# SCH_Arduino_Nano_ESP32_CapibaraZero_2024.net
KiCad netlist of a schematic drawn in EasyEDA
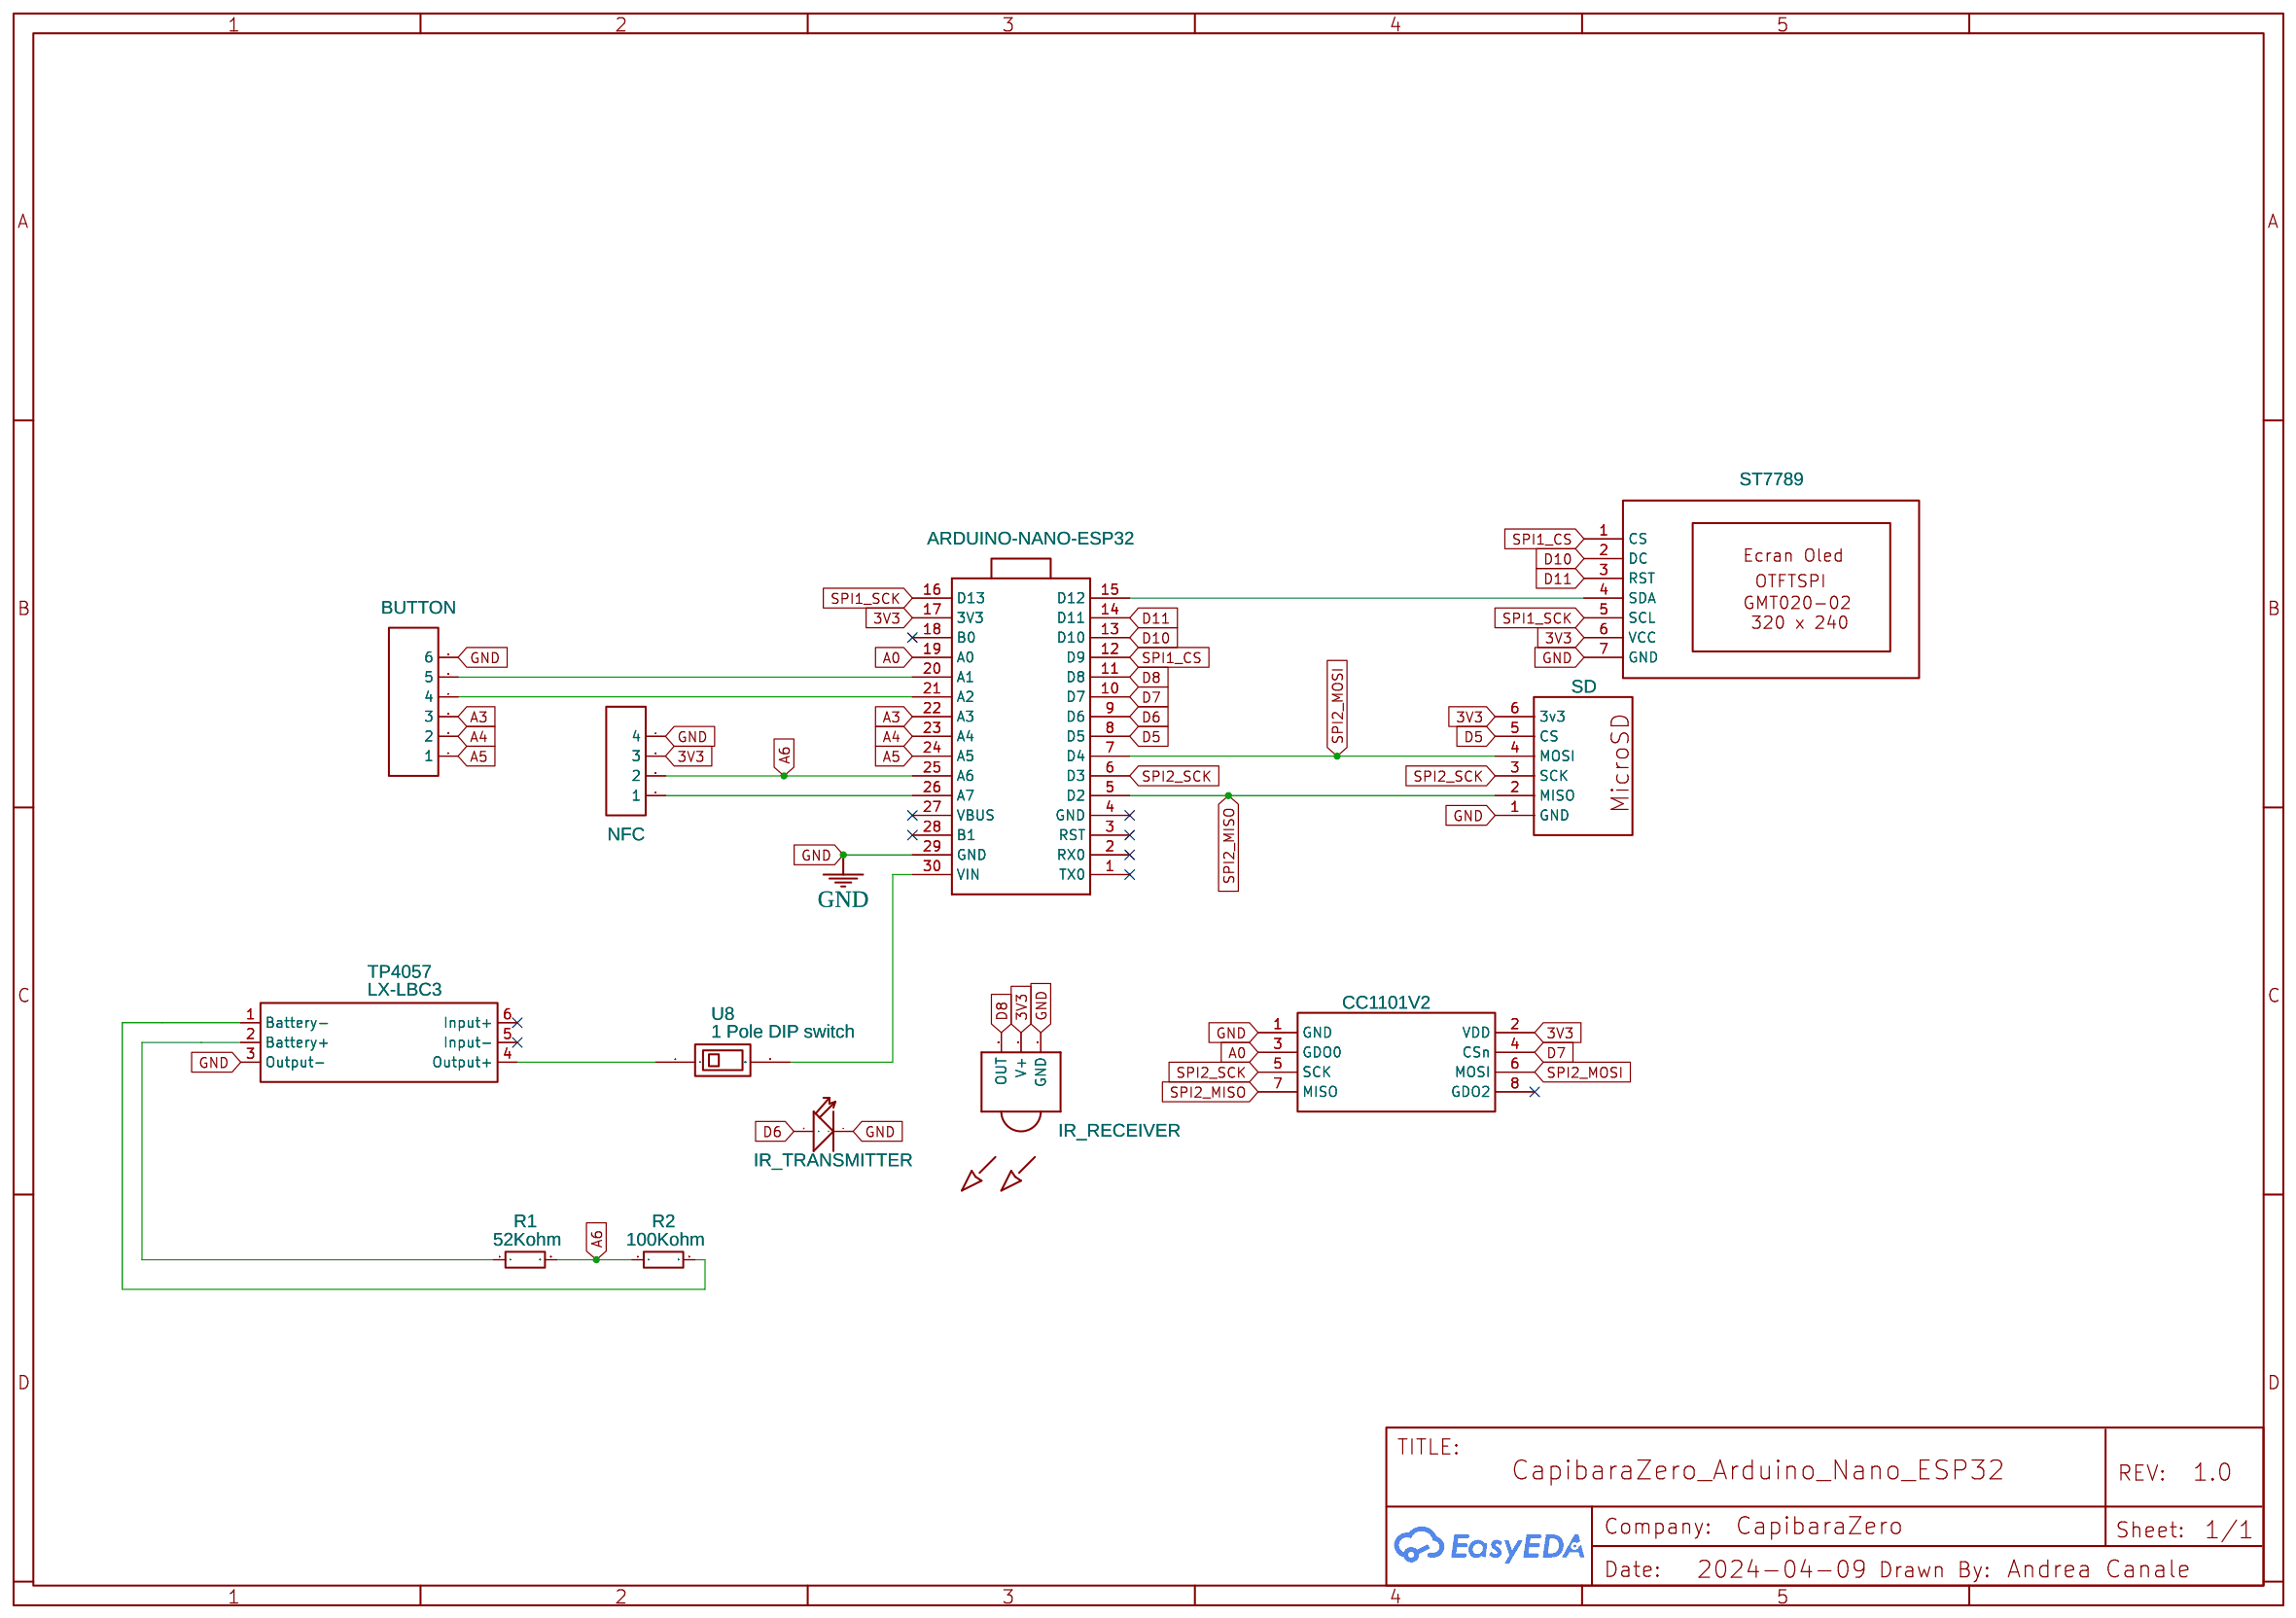
[diagram p0: MainScheme]
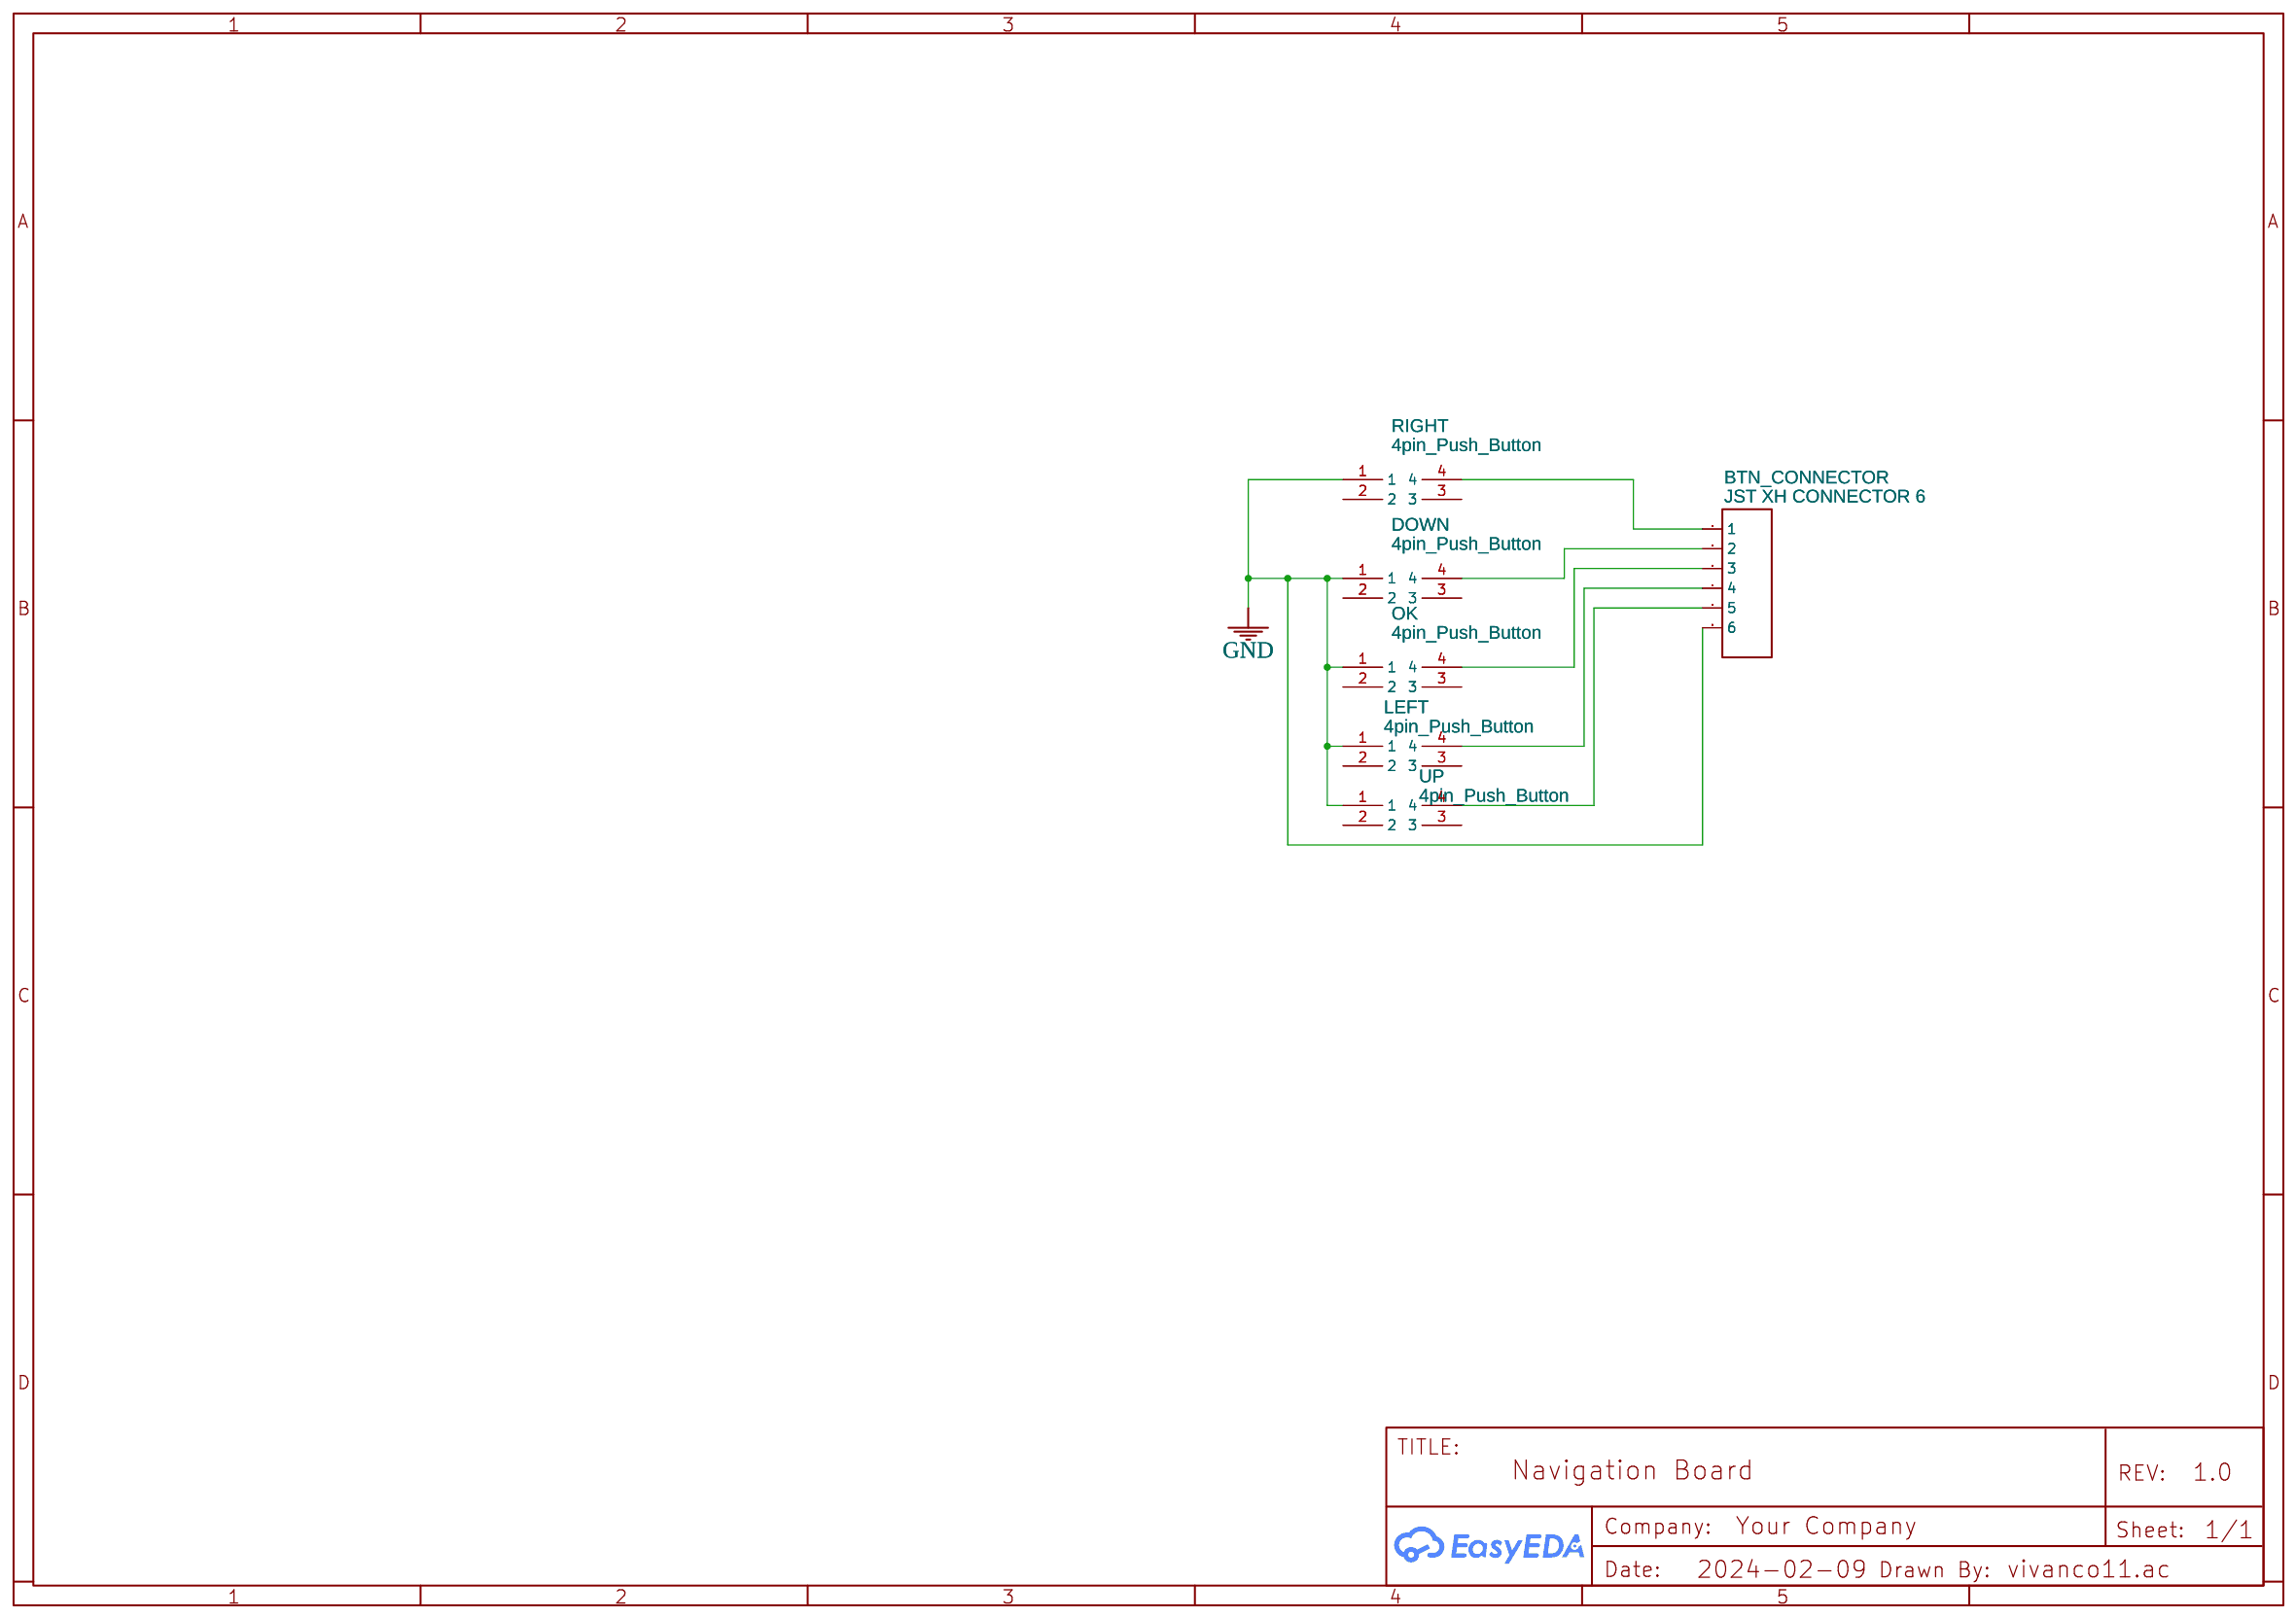
[diagram p1: Navigation_board]

(export (version "E")
  (design (tool "Eeschema 10.0.6"))
  (components
    (comp (ref "ARDUINO-NANO-ESP32")
      (value "ARDUINO-NANO-ESP32")
      (fields (field (name "Manufacturer") "Arduino"))
      (libsource (lib "") (part "ARDUINO-NANO-ESP32"))
    )
    (comp (ref "BUTTON")
      (value "BTN Connector")
      (fields (field (name "Manufacturer Part") "JST_XH CONNECTOR"))
      (libsource (lib "") (part "JST XH CONNECTOR 6"))
    )
    (comp (ref "CC1101V2")
      (value "CC1101 E07-M1101D")
      (fields
        (field (name "Manufacturer Part") "E07-M1101D-SMA")
        (field (name "Manufacturer") "Chengdu Ebyte Electronic Technology Co., Ltd.")
      )
      (libsource (lib "") (part "CC1101 E07-M1101D"))
    )
    (comp (ref "IR_RECEIVER") (value "IR Receiver") (libsource (lib "") (part "IR TRANSMITTER")))
    (comp (ref "IR_TRANSMITTER")
      (value "DIP-IR-LED-940NM(2P-D5MM)")
      (fields (field (name "Manufacturer Part") "IR523B-W60W1"))
      (libsource (lib "") (part "DIP-IR-LED-940NM(2P-D5MM)"))
    )
    (comp (ref "NFC")
      (value "NFC Connector")
      (fields (field (name "Manufacturer Part") "JST_XH CONNECTOR"))
      (libsource (lib "") (part "JST XH CONNECTOR 4"))
    )
    (comp (ref "R1")
      (value "52Kohm")
      (fields
        (field (name "Manufacturer Part") "EWWR0001J20R0T9")
        (field (name "Manufacturer") "ResistorToday")
      )
      (libsource (lib "") (part "Resistor Normal"))
    )
    (comp (ref "R2")
      (value "100Kohm")
      (fields
        (field (name "Manufacturer Part") "EWWR0001J20R0T9")
        (field (name "Manufacturer") "ResistorToday")
      )
      (libsource (lib "") (part "Resistor Normal"))
    )
    (comp (ref "SD") (value "MicroSDSPI") (libsource (lib "") (part "MicroSDSPI")))
    (comp (ref "ST7789")
      (value "ST7789_Display_320x240_SPI")
      (libsource (lib "") (part "ST7789_Display_320x240_SPI"))
    )
    (comp (ref "TP4057") (value "LX-LBC3") (libsource (lib "") (part "LX-LBC3")))
    (comp (ref "U8") (value "1 Pole DIP switch") (libsource (lib "") (part "1 Pole DIP switch")))
    (comp (ref "BTN_CONNECTOR")
      (value "JST XH CONNECTOR 6")
      (fields (field (name "Manufacturer Part") "JST_XH CONNECTOR"))
      (libsource (lib "") (part "JST XH CONNECTOR 6"))
    )
    (comp (ref "DOWN") (value "4pin_Push_Button") (libsource (lib "") (part "4pin_Push_Button_2")))
    (comp (ref "LEFT") (value "4pin_Push_Button") (libsource (lib "") (part "4pin_Push_Button_4")))
    (comp (ref "OK") (value "4pin_Push_Button") (libsource (lib "") (part "4pin_Push_Button_3")))
    (comp (ref "RIGHT") (value "4pin_Push_Button") (libsource (lib "") (part "4pin_Push_Button")))
    (comp (ref "UP") (value "4pin_Push_Button") (libsource (lib "") (part "4pin_Push_Button_1")))
  )
  (nets
    (net (code "1") (name "3V3") (class "Default")
      (node (ref "ARDUINO-NANO-ESP32") (pin "17") (pinfunction "3V3_17") (pintype "unspecified"))
      (node (ref "CC1101V2") (pin "2") (pinfunction "VDD_2") (pintype "unspecified"))
      (node (ref "IR_RECEIVER") (pin "VCC") (pinfunction "V+_VCC") (pintype "unspecified"))
      (node (ref "NFC") (pin "3") (pinfunction "3_3") (pintype "unspecified"))
      (node (ref "SD") (pin "6") (pinfunction "3v3_6") (pintype "unspecified"))
      (node (ref "ST7789") (pin "6") (pinfunction "VCC_6") (pintype "unspecified"))
    )
    (net (code "2") (name "A0") (class "Default")
      (node (ref "ARDUINO-NANO-ESP32") (pin "19") (pinfunction "A0_19") (pintype "unspecified"))
      (node (ref "CC1101V2") (pin "3") (pinfunction "GDO0_3") (pintype "unspecified"))
    )
    (net (code "3") (name "A3") (class "Default")
      (node (ref "ARDUINO-NANO-ESP32") (pin "22") (pinfunction "A3_22") (pintype "unspecified"))
      (node (ref "BUTTON") (pin "3") (pinfunction "3_3") (pintype "unspecified"))
    )
    (net (code "4") (name "A4") (class "Default")
      (node (ref "ARDUINO-NANO-ESP32") (pin "23") (pinfunction "A4_23") (pintype "unspecified"))
      (node (ref "BUTTON") (pin "2") (pinfunction "2_2") (pintype "unspecified"))
    )
    (net (code "5") (name "A5") (class "Default")
      (node (ref "ARDUINO-NANO-ESP32") (pin "24") (pinfunction "A5_24") (pintype "unspecified"))
      (node (ref "BUTTON") (pin "1") (pinfunction "1_1") (pintype "unspecified"))
    )
    (net (code "6") (name "A6") (class "Default")
      (node (ref "ARDUINO-NANO-ESP32") (pin "25") (pinfunction "A6_25") (pintype "unspecified"))
      (node (ref "NFC") (pin "2") (pinfunction "2_2") (pintype "unspecified"))
      (node (ref "R1") (pin "2") (pinfunction "2_2") (pintype "unspecified"))
      (node (ref "R2") (pin "1") (pinfunction "1_1") (pintype "unspecified"))
    )
    (net (code "7") (name "D5") (class "Default")
      (node (ref "ARDUINO-NANO-ESP32") (pin "8") (pinfunction "D5_8") (pintype "unspecified"))
      (node (ref "SD") (pin "5") (pinfunction "CS_5") (pintype "unspecified"))
    )
    (net (code "8") (name "D6") (class "Default")
      (node (ref "ARDUINO-NANO-ESP32") (pin "9") (pinfunction "D6_9") (pintype "unspecified"))
      (node (ref "IR_TRANSMITTER") (pin "+") (pinfunction "+_+") (pintype "unspecified"))
    )
    (net (code "9") (name "D7") (class "Default")
      (node (ref "ARDUINO-NANO-ESP32") (pin "10") (pinfunction "D7_10") (pintype "unspecified"))
      (node (ref "CC1101V2") (pin "4") (pinfunction "CSn_4") (pintype "unspecified"))
    )
    (net (code "10") (name "D8") (class "Default")
      (node (ref "ARDUINO-NANO-ESP32") (pin "11") (pinfunction "D8_11") (pintype "unspecified"))
      (node (ref "IR_RECEIVER") (pin "OUT") (pinfunction "OUT_OUT") (pintype "unspecified"))
    )
    (net (code "11") (name "D10") (class "Default")
      (node (ref "ARDUINO-NANO-ESP32") (pin "13") (pinfunction "D10_13") (pintype "unspecified"))
      (node (ref "ST7789") (pin "2") (pinfunction "DC_2") (pintype "unspecified"))
    )
    (net (code "12") (name "D11") (class "Default")
      (node (ref "ARDUINO-NANO-ESP32") (pin "14") (pinfunction "D11_14") (pintype "unspecified"))
      (node (ref "ST7789") (pin "3") (pinfunction "RST_3") (pintype "unspecified"))
    )
    (net (code "13") (name "GND") (class "Default")
      (node (ref "ARDUINO-NANO-ESP32") (pin "29") (pinfunction "GND_29") (pintype "unspecified"))
      (node (ref "BTN_CONNECTOR") (pin "6") (pinfunction "6_6") (pintype "unspecified"))
      (node (ref "BUTTON") (pin "6") (pinfunction "6_6") (pintype "unspecified"))
      (node (ref "CC1101V2") (pin "1") (pinfunction "GND_1") (pintype "unspecified"))
      (node (ref "DOWN") (pin "1") (pinfunction "1_1") (pintype "unspecified"))
      (node (ref "IR_RECEIVER") (pin "GND") (pinfunction "GND_GND") (pintype "unspecified"))
      (node (ref "IR_TRANSMITTER") (pin "-") (pinfunction "-_-") (pintype "unspecified"))
      (node (ref "LEFT") (pin "1") (pinfunction "1_1") (pintype "unspecified"))
      (node (ref "NFC") (pin "4") (pinfunction "4_4") (pintype "unspecified"))
      (node (ref "OK") (pin "1") (pinfunction "1_1") (pintype "unspecified"))
      (node (ref "RIGHT") (pin "1") (pinfunction "1_1") (pintype "unspecified"))
      (node (ref "SD") (pin "1") (pinfunction "GND_1") (pintype "unspecified"))
      (node (ref "ST7789") (pin "7") (pinfunction "GND_7") (pintype "unspecified"))
      (node (ref "TP4057") (pin "3") (pinfunction "Output-_3") (pintype "unspecified"))
      (node (ref "UP") (pin "1") (pinfunction "1_1") (pintype "unspecified"))
    )
    (net (code "14") (name "Net-(ARDUINO-NANO-ESP32-A1)") (class "Default")
      (node (ref "ARDUINO-NANO-ESP32") (pin "20") (pinfunction "A1_20") (pintype "unspecified"))
      (node (ref "BUTTON") (pin "5") (pinfunction "5_5") (pintype "unspecified"))
    )
    (net (code "15") (name "Net-(ARDUINO-NANO-ESP32-A2)") (class "Default")
      (node (ref "ARDUINO-NANO-ESP32") (pin "21") (pinfunction "A2_21") (pintype "unspecified"))
      (node (ref "BUTTON") (pin "4") (pinfunction "4_4") (pintype "unspecified"))
    )
    (net (code "16") (name "Net-(ARDUINO-NANO-ESP32-A7)") (class "Default")
      (node (ref "ARDUINO-NANO-ESP32") (pin "26") (pinfunction "A7_26") (pintype "unspecified"))
      (node (ref "NFC") (pin "1") (pinfunction "1_1") (pintype "unspecified"))
    )
    (net (code "17") (name "Net-(ARDUINO-NANO-ESP32-D12)") (class "Default")
      (node (ref "ARDUINO-NANO-ESP32") (pin "15") (pinfunction "D12_15") (pintype "unspecified"))
      (node (ref "ST7789") (pin "4") (pinfunction "SDA_4") (pintype "unspecified"))
    )
    (net (code "18") (name "Net-(ARDUINO-NANO-ESP32-VIN)") (class "Default")
      (node (ref "ARDUINO-NANO-ESP32") (pin "30") (pinfunction "VIN_30") (pintype "unspecified"))
      (node (ref "U8") (pin "2") (pinfunction "OUT_2") (pintype "unspecified"))
    )
    (net (code "19") (name "Net-(BTN_CONNECTOR-Pad1)") (class "Default")
      (node (ref "BTN_CONNECTOR") (pin "1") (pinfunction "1_1") (pintype "unspecified"))
      (node (ref "RIGHT") (pin "4") (pinfunction "4_4") (pintype "unspecified"))
    )
    (net (code "20") (name "Net-(BTN_CONNECTOR-Pad2)") (class "Default")
      (node (ref "BTN_CONNECTOR") (pin "2") (pinfunction "2_2") (pintype "unspecified"))
      (node (ref "DOWN") (pin "4") (pinfunction "4_4") (pintype "unspecified"))
    )
    (net (code "21") (name "Net-(BTN_CONNECTOR-Pad3)") (class "Default")
      (node (ref "BTN_CONNECTOR") (pin "3") (pinfunction "3_3") (pintype "unspecified"))
      (node (ref "OK") (pin "4") (pinfunction "4_4") (pintype "unspecified"))
    )
    (net (code "22") (name "Net-(BTN_CONNECTOR-Pad4)") (class "Default")
      (node (ref "BTN_CONNECTOR") (pin "4") (pinfunction "4_4") (pintype "unspecified"))
      (node (ref "LEFT") (pin "4") (pinfunction "4_4") (pintype "unspecified"))
    )
    (net (code "23") (name "Net-(BTN_CONNECTOR-Pad5)") (class "Default")
      (node (ref "BTN_CONNECTOR") (pin "5") (pinfunction "5_5") (pintype "unspecified"))
      (node (ref "UP") (pin "4") (pinfunction "4_4") (pintype "unspecified"))
    )
    (net (code "24") (name "Net-(TP4057-Battery+)") (class "Default")
      (node (ref "R1") (pin "1") (pinfunction "1_1") (pintype "unspecified"))
      (node (ref "TP4057") (pin "2") (pinfunction "Battery+_2") (pintype "unspecified"))
    )
    (net (code "25") (name "Net-(TP4057-Battery-)") (class "Default")
      (node (ref "R2") (pin "2") (pinfunction "2_2") (pintype "unspecified"))
      (node (ref "TP4057") (pin "1") (pinfunction "Battery-_1") (pintype "unspecified"))
    )
    (net (code "26") (name "Net-(TP4057-Output+)") (class "Default")
      (node (ref "TP4057") (pin "4") (pinfunction "Output+_4") (pintype "unspecified"))
      (node (ref "U8") (pin "1") (pinfunction "IN_1") (pintype "unspecified"))
    )
    (net (code "27") (name "SPI1_CS") (class "Default")
      (node (ref "ARDUINO-NANO-ESP32") (pin "12") (pinfunction "D9_12") (pintype "unspecified"))
      (node (ref "ST7789") (pin "1") (pinfunction "CS_1") (pintype "unspecified"))
    )
    (net (code "28") (name "SPI1_SCK") (class "Default")
      (node (ref "ARDUINO-NANO-ESP32") (pin "16") (pinfunction "D13_16") (pintype "unspecified"))
      (node (ref "ST7789") (pin "5") (pinfunction "SCL_5") (pintype "unspecified"))
    )
    (net (code "29") (name "SPI2_MISO") (class "Default")
      (node (ref "ARDUINO-NANO-ESP32") (pin "5") (pinfunction "D2_5") (pintype "unspecified"))
      (node (ref "CC1101V2") (pin "7") (pinfunction "MISO_7") (pintype "unspecified"))
      (node (ref "SD") (pin "2") (pinfunction "MISO_2") (pintype "unspecified"))
    )
    (net (code "30") (name "SPI2_MOSI") (class "Default")
      (node (ref "ARDUINO-NANO-ESP32") (pin "7") (pinfunction "D4_7") (pintype "unspecified"))
      (node (ref "CC1101V2") (pin "6") (pinfunction "MOSI_6") (pintype "unspecified"))
      (node (ref "SD") (pin "4") (pinfunction "MOSI_4") (pintype "unspecified"))
    )
    (net (code "31") (name "SPI2_SCK") (class "Default")
      (node (ref "ARDUINO-NANO-ESP32") (pin "6") (pinfunction "D3_6") (pintype "unspecified"))
      (node (ref "CC1101V2") (pin "5") (pinfunction "SCK_5") (pintype "unspecified"))
      (node (ref "SD") (pin "3") (pinfunction "SCK_3") (pintype "unspecified"))
    )
    (net (code "32") (name "unconnected-(ARDUINO-NANO-ESP32-B0-Pad18)") (class "Default")
      (node (ref "ARDUINO-NANO-ESP32") (pin "18") (pinfunction "B0_18") (pintype "unspecified+no_connect"))
    )
    (net (code "33") (name "unconnected-(ARDUINO-NANO-ESP32-B1-Pad28)") (class "Default")
      (node (ref "ARDUINO-NANO-ESP32") (pin "28") (pinfunction "B1_28") (pintype "unspecified+no_connect"))
    )
    (net (code "34") (name "unconnected-(ARDUINO-NANO-ESP32-GND-Pad4)") (class "Default")
      (node (ref "ARDUINO-NANO-ESP32") (pin "4") (pinfunction "GND_4") (pintype "unspecified+no_connect"))
    )
    (net (code "35") (name "unconnected-(ARDUINO-NANO-ESP32-RST-Pad3)") (class "Default")
      (node (ref "ARDUINO-NANO-ESP32") (pin "3") (pinfunction "RST_3") (pintype "unspecified+no_connect"))
    )
    (net (code "36") (name "unconnected-(ARDUINO-NANO-ESP32-RX0-Pad2)") (class "Default")
      (node (ref "ARDUINO-NANO-ESP32") (pin "2") (pinfunction "RX0_2") (pintype "unspecified+no_connect"))
    )
    (net (code "37") (name "unconnected-(ARDUINO-NANO-ESP32-TX0-Pad1)") (class "Default")
      (node (ref "ARDUINO-NANO-ESP32") (pin "1") (pinfunction "TX0_1") (pintype "unspecified+no_connect"))
    )
    (net (code "38") (name "unconnected-(ARDUINO-NANO-ESP32-VBUS-Pad27)") (class "Default")
      (node (ref "ARDUINO-NANO-ESP32") (pin "27") (pinfunction "VBUS_27") (pintype "unspecified+no_connect"))
    )
    (net (code "39") (name "unconnected-(CC1101V2-GDO2-Pad8)") (class "Default")
      (node (ref "CC1101V2") (pin "8") (pinfunction "GDO2_8") (pintype "unspecified+no_connect"))
    )
    (net (code "40") (name "unconnected-(DOWN-Pad2)") (class "Default")
      (node (ref "DOWN") (pin "2") (pinfunction "2_2") (pintype "unspecified"))
    )
    (net (code "41") (name "unconnected-(DOWN-Pad3)") (class "Default")
      (node (ref "DOWN") (pin "3") (pinfunction "3_3") (pintype "unspecified"))
    )
    (net (code "42") (name "unconnected-(LEFT-Pad2)") (class "Default")
      (node (ref "LEFT") (pin "2") (pinfunction "2_2") (pintype "unspecified"))
    )
    (net (code "43") (name "unconnected-(LEFT-Pad3)") (class "Default")
      (node (ref "LEFT") (pin "3") (pinfunction "3_3") (pintype "unspecified"))
    )
    (net (code "44") (name "unconnected-(OK-Pad2)") (class "Default")
      (node (ref "OK") (pin "2") (pinfunction "2_2") (pintype "unspecified"))
    )
    (net (code "45") (name "unconnected-(OK-Pad3)") (class "Default")
      (node (ref "OK") (pin "3") (pinfunction "3_3") (pintype "unspecified"))
    )
    (net (code "46") (name "unconnected-(RIGHT-Pad2)") (class "Default")
      (node (ref "RIGHT") (pin "2") (pinfunction "2_2") (pintype "unspecified"))
    )
    (net (code "47") (name "unconnected-(RIGHT-Pad3)") (class "Default")
      (node (ref "RIGHT") (pin "3") (pinfunction "3_3") (pintype "unspecified"))
    )
    (net (code "48") (name "unconnected-(TP4057-Input+-Pad6)") (class "Default")
      (node (ref "TP4057") (pin "6") (pinfunction "Input+_6") (pintype "unspecified+no_connect"))
    )
    (net (code "49") (name "unconnected-(TP4057-Input--Pad5)") (class "Default")
      (node (ref "TP4057") (pin "5") (pinfunction "Input-_5") (pintype "unspecified+no_connect"))
    )
    (net (code "50") (name "unconnected-(UP-Pad2)") (class "Default")
      (node (ref "UP") (pin "2") (pinfunction "2_2") (pintype "unspecified"))
    )
    (net (code "51") (name "unconnected-(UP-Pad3)") (class "Default")
      (node (ref "UP") (pin "3") (pinfunction "3_3") (pintype "unspecified"))
    )
  )
)
